# MCUandExtra.net
KiCad netlist of a schematic drawn in Altium Designer
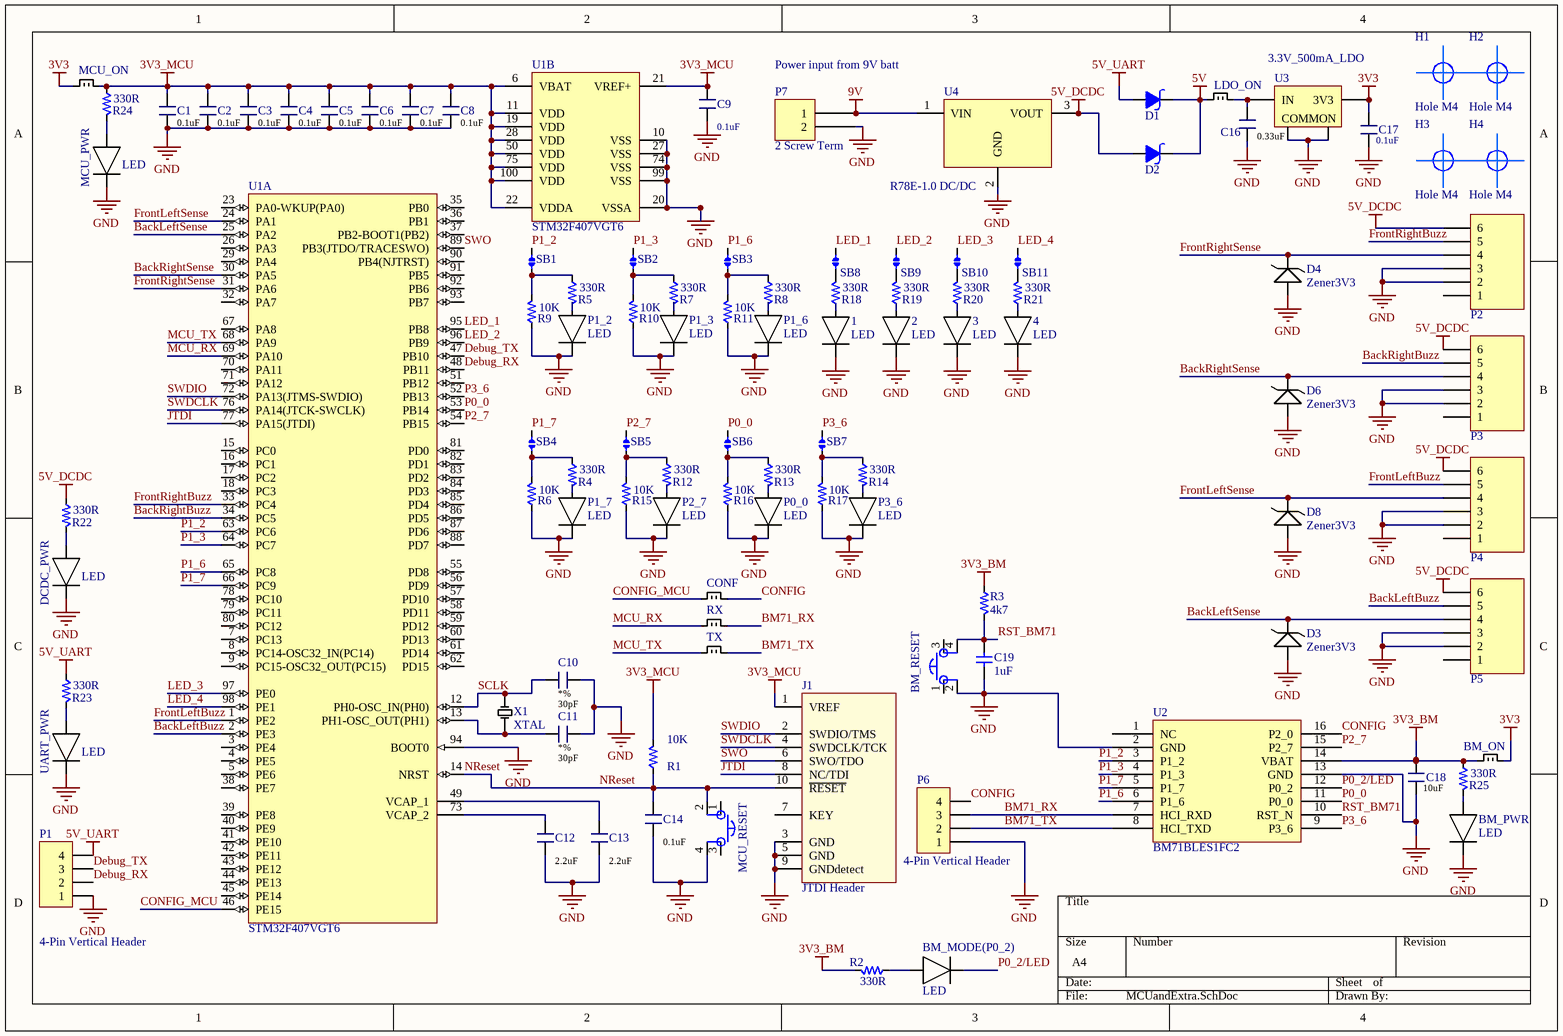
[diagram p0: MCUandExtra.SchDoc]

(export (version "E")
  (design (tool "Eeschema 10.0.6"))
  (components
    (comp (ref "1")
      (value "LED")
      (footprint "SMD_0603_LED")
      (libsource (lib "0603 LED") (part "SMD_0603_LED"))
    )
    (comp (ref "2")
      (value "LED")
      (footprint "SMD_0603_LED")
      (libsource (lib "0603 LED") (part "SMD_0603_LED"))
    )
    (comp (ref "3")
      (value "LED")
      (footprint "SMD_0603_LED")
      (libsource (lib "0603 LED") (part "SMD_0603_LED"))
    )
    (comp (ref "4")
      (value "LED")
      (footprint "SMD_0603_LED")
      (libsource (lib "0603 LED") (part "SMD_0603_LED"))
    )
    (comp (ref "BM_MODE(P0_2)")
      (value "LED")
      (footprint "SMD_0603_LED")
      (libsource (lib "0603 LED") (part "SMD_0603_LED"))
    )
    (comp (ref "BM_ON")
      (value "2.54Jump")
      (footprint "Jumper")
      (description "WM23943-ND")
      (libsource (lib "2.54HeaderJumper") (part "Jumper"))
    )
    (comp (ref "BM_PWR")
      (value "LED")
      (footprint "SMD_0603_LED")
      (libsource (lib "0603 LED") (part "SMD_0603_LED"))
    )
    (comp (ref "BM_RESET")
      (value "Tactile Switch")
      (footprint "C&K 4 pin Tactile Switch")
      (libsource (lib "C&K 4 Pin Tactile Switch") (part "C&K Tactile Switch"))
    )
    (comp (ref "C1")
      (value "SCH_GENERIC_CAPACITOR_0603")
      (footprint "PCB_GENERIC_SMD_0603")
      (description "Generic SMD capacitor 0603")
      (fields (field (name "TOLERANCE") "*%") (field (name "CAPACITANCE") "0.1uF"))
      (libsource (lib "Generic 0603 Capacitor") (part "SCH_GENERIC_CAPACITOR_0603"))
    )
    (comp (ref "C2")
      (value "SCH_GENERIC_CAPACITOR_0603")
      (footprint "PCB_GENERIC_SMD_0603")
      (description "Generic SMD capacitor 0603")
      (fields (field (name "TOLERANCE") "*%") (field (name "CAPACITANCE") "0.1uF"))
      (libsource (lib "Generic 0603 Capacitor") (part "SCH_GENERIC_CAPACITOR_0603"))
    )
    (comp (ref "C3")
      (value "SCH_GENERIC_CAPACITOR_0603")
      (footprint "PCB_GENERIC_SMD_0603")
      (description "Generic SMD capacitor 0603")
      (fields (field (name "TOLERANCE") "*%") (field (name "CAPACITANCE") "0.1uF"))
      (libsource (lib "Generic 0603 Capacitor") (part "SCH_GENERIC_CAPACITOR_0603"))
    )
    (comp (ref "C4")
      (value "SCH_GENERIC_CAPACITOR_0603")
      (footprint "PCB_GENERIC_SMD_0603")
      (description "Generic SMD capacitor 0603")
      (fields (field (name "TOLERANCE") "*%") (field (name "CAPACITANCE") "0.1uF"))
      (libsource (lib "Generic 0603 Capacitor") (part "SCH_GENERIC_CAPACITOR_0603"))
    )
    (comp (ref "C5")
      (value "SCH_GENERIC_CAPACITOR_0603")
      (footprint "PCB_GENERIC_SMD_0603")
      (description "Generic SMD capacitor 0603")
      (fields (field (name "TOLERANCE") "*%") (field (name "CAPACITANCE") "0.1uF"))
      (libsource (lib "Generic 0603 Capacitor") (part "SCH_GENERIC_CAPACITOR_0603"))
    )
    (comp (ref "C6")
      (value "SCH_GENERIC_CAPACITOR_0603")
      (footprint "PCB_GENERIC_SMD_0603")
      (description "Generic SMD capacitor 0603")
      (fields (field (name "TOLERANCE") "*%") (field (name "CAPACITANCE") "0.1uF"))
      (libsource (lib "Generic 0603 Capacitor") (part "SCH_GENERIC_CAPACITOR_0603"))
    )
    (comp (ref "C7")
      (value "SCH_GENERIC_CAPACITOR_0603")
      (footprint "PCB_GENERIC_SMD_0603")
      (description "Generic SMD capacitor 0603")
      (fields (field (name "TOLERANCE") "*%") (field (name "CAPACITANCE") "0.1uF"))
      (libsource (lib "Generic 0603 Capacitor") (part "SCH_GENERIC_CAPACITOR_0603"))
    )
    (comp (ref "C8")
      (value "SCH_GENERIC_CAPACITOR_0603")
      (footprint "PCB_GENERIC_SMD_0603")
      (description "Generic SMD capacitor 0603")
      (fields (field (name "TOLERANCE") "*%") (field (name "CAPACITANCE") "0.1uF"))
      (libsource (lib "Generic 0603 Capacitor") (part "SCH_GENERIC_CAPACITOR_0603"))
    )
    (comp (ref "C9")
      (value "SCH_GENERIC_CAPACITOR_0603")
      (footprint "PCB_GENERIC_SMD_0603")
      (description "Generic SMD capacitor 0603")
      (fields (field (name "CAPACITANCE") "0.1uF"))
      (libsource (lib "Generic 0603 Capacitor") (part "SCH_GENERIC_CAPACITOR_0603"))
    )
    (comp (ref "C10")
      (value "SCH_GENERIC_CAPACITOR_0603")
      (footprint "PCB_GENERIC_SMD_0603")
      (description "Generic SMD capacitor 0603")
      (fields (field (name "TOLERANCE") "*%") (field (name "CAPACITANCE") "30pF"))
      (libsource (lib "Capacitors") (part "SCH_GENERIC_CAPACITOR_0603"))
    )
    (comp (ref "C11")
      (value "SCH_GENERIC_CAPACITOR_0603")
      (footprint "PCB_GENERIC_SMD_0603")
      (description "Generic SMD capacitor 0603")
      (fields (field (name "TOLERANCE") "*%") (field (name "CAPACITANCE") "30pF"))
      (libsource (lib "Capacitors") (part "SCH_GENERIC_CAPACITOR_0603"))
    )
    (comp (ref "C12")
      (value "SCH_GENERIC_CAPACITOR_0603")
      (footprint "PCB_GENERIC_SMD_0603")
      (description "Generic SMD capacitor 0603")
      (fields (field (name "TOLERANCE") "*%") (field (name "CAPACITANCE") "2.2uF"))
      (libsource (lib "Capacitors") (part "SCH_GENERIC_CAPACITOR_0603"))
    )
    (comp (ref "C13")
      (value "SCH_GENERIC_CAPACITOR_0603")
      (footprint "PCB_GENERIC_SMD_0603")
      (description "Generic SMD capacitor 0603")
      (fields (field (name "TOLERANCE") "*%") (field (name "CAPACITANCE") "2.2uF"))
      (libsource (lib "Capacitors") (part "SCH_GENERIC_CAPACITOR_0603"))
    )
    (comp (ref "C14")
      (value "SCH_GENERIC_CAPACITOR_0603")
      (footprint "PCB_GENERIC_SMD_0603")
      (description "Generic SMD capacitor 0603")
      (fields (field (name "TOLERANCE") "*%") (field (name "CAPACITANCE") "0.1uF"))
      (libsource (lib "Capacitors") (part "SCH_GENERIC_CAPACITOR_0603"))
    )
    (comp (ref "C16")
      (value "SCH_GENERIC_CAPACITOR_0603")
      (footprint "PCB_GENERIC_SMD_0603")
      (description "Generic SMD capacitor 0603")
      (fields (field (name "CAPACITANCE") "0.33uF") (field (name "TOLERANCE") "*%"))
      (libsource (lib "Generic 0603 Capacitor") (part "SCH_GENERIC_CAPACITOR_0603"))
    )
    (comp (ref "C17")
      (value "SCH_GENERIC_CAPACITOR_0603")
      (footprint "PCB_GENERIC_SMD_0603")
      (description "Generic SMD capacitor 0603")
      (fields (field (name "CAPACITANCE") "0.1uF"))
      (libsource (lib "Generic 0603 Capacitor") (part "SCH_GENERIC_CAPACITOR_0603"))
    )
    (comp (ref "C18")
      (value "SCH_GENERIC_CAPACITOR_0603")
      (footprint "PCB_GENERIC_SMD_0603")
      (description "Generic SMD capacitor 0603")
      (fields (field (name "TOLERANCE") "*%") (field (name "CAPACITANCE") "10uF"))
      (libsource (lib "Capacitors") (part "SCH_GENERIC_CAPACITOR_0603"))
    )
    (comp (ref "C19")
      (value "1uF")
      (footprint "PCB_GENERIC_SMD_0603")
      (description "CAP CER 0603 1uF 16V X5R 20%")
      (fields (field (name "TOLERANCE") "20%") (field (name "VOLTAGE") "16V"))
      (libsource (lib "CAP-0603") (part "C060-0001U-00"))
    )
    (comp (ref "CONF")
      (value "2.54Jump")
      (footprint "Jumper")
      (description "WM23943-ND")
      (libsource (lib "2.54HeaderJumper") (part "Jumper"))
    )
    (comp (ref "D1")
      (value "ONSEMI_MBRM110LT1G")
      (footprint "ON Semi Schottky Diode - MBRM110LT1G")
      (description "DIODE SCHOTTKY 10V 1A")
      (libsource (lib "ON Semi Schottky Diode") (part "ONSEMI_MBRM110LT1G"))
    )
    (comp (ref "D2")
      (value "ONSEMI_MBRM110LT1G")
      (footprint "ON Semi Schottky Diode - MBRM110LT1G")
      (description "DIODE SCHOTTKY 10V 1A")
      (libsource (lib "ON Semi Schottky Diode") (part "ONSEMI_MBRM110LT1G"))
    )
    (comp (ref "D3")
      (value "Zener3V3")
      (footprint "Zener3V3")
      (description "DZ2W03300LCT-ND")
      (libsource (lib "Zener3V3") (part "DZ2W03300LCT-ND"))
    )
    (comp (ref "D4")
      (value "Zener3V3")
      (footprint "Zener3V3")
      (description "DZ2W03300LCT-ND")
      (libsource (lib "Zener3V3") (part "DZ2W03300LCT-ND"))
    )
    (comp (ref "D6")
      (value "Zener3V3")
      (footprint "Zener3V3")
      (description "DZ2W03300LCT-ND")
      (libsource (lib "Zener3V3") (part "DZ2W03300LCT-ND"))
    )
    (comp (ref "D8")
      (value "Zener3V3")
      (footprint "Zener3V3")
      (description "DZ2W03300LCT-ND")
      (libsource (lib "Zener3V3") (part "DZ2W03300LCT-ND"))
    )
    (comp (ref "DCDC_PWR")
      (value "LED")
      (footprint "SMD_0603_LED")
      (libsource (lib "0603 LED") (part "SMD_0603_LED"))
    )
    (comp (ref "H1") (value "Hole M4") (footprint "M4_Hole") (libsource (lib "M4") (part "Component_1")))
    (comp (ref "H2") (value "Hole M4") (footprint "M4_Hole") (libsource (lib "M4") (part "Component_1")))
    (comp (ref "H3") (value "Hole M4") (footprint "M4_Hole") (libsource (lib "M4") (part "Component_1")))
    (comp (ref "H4") (value "Hole M4") (footprint "M4_Hole") (libsource (lib "M4") (part "Component_1")))
    (comp (ref "J1")
      (value "JTDI Header")
      (footprint "CONN-50mil-10POS-SMD")
      (description "ARM Cortex-M 10pin connector,shrouded,SMT")
      (libsource (lib "CONN-50mil-cortexM") (part "conn_0.050{dblquote}_cortexM"))
    )
    (comp (ref "LDO_ON")
      (value "2.54Jump")
      (footprint "Jumper")
      (description "WM23943-ND")
      (libsource (lib "2.54HeaderJumper") (part "Jumper"))
    )
    (comp (ref "MCU_ON")
      (value "2.54Jump")
      (footprint "Jumper")
      (description "WM23943-ND")
      (libsource (lib "2.54HeaderJumper") (part "Jumper"))
    )
    (comp (ref "MCU_PWR")
      (value "LED")
      (footprint "SMD_0603_LED")
      (libsource (lib "0603 LED") (part "SMD_0603_LED"))
    )
    (comp (ref "MCU_RESET")
      (value "Tactile Switch")
      (footprint "C&K 4 pin Tactile Switch")
      (libsource (lib "C&K 4 Pin Tactile Switch") (part "C&K Tactile Switch"))
    )
    (comp (ref "P0_0")
      (value "LED")
      (footprint "SMD_0603_LED")
      (libsource (lib "0603 LED") (part "SMD_0603_LED"))
    )
    (comp (ref "P1")
      (value "4-Pin Vertical Header")
      (footprint "4-Pin Vertical Header")
      (fields (field (name "MANUFACTURER") "Sullins"))
      (libsource (lib "4 Pin 100 mil Vertical Header - Through Hole") (part "4-Pin Vertical Header"))
    )
    (comp (ref "P1_2")
      (value "LED")
      (footprint "SMD_0603_LED")
      (libsource (lib "0603 LED") (part "SMD_0603_LED"))
    )
    (comp (ref "P1_3")
      (value "LED")
      (footprint "SMD_0603_LED")
      (libsource (lib "0603 LED") (part "SMD_0603_LED"))
    )
    (comp (ref "P1_6")
      (value "LED")
      (footprint "SMD_0603_LED")
      (libsource (lib "0603 LED") (part "SMD_0603_LED"))
    )
    (comp (ref "P1_7")
      (value "LED")
      (footprint "SMD_0603_LED")
      (libsource (lib "0603 LED") (part "SMD_0603_LED"))
    )
    (comp (ref "P2")
      (value "SCH_MLX_MICROFIT_3X2")
      (footprint "PCB_MLX_MICROFIT_3X2")
      (libsource (lib "Molex Microfit 3.0 3x2") (part "SCH_MLX_MICROFIT_3X2"))
    )
    (comp (ref "P2_7")
      (value "LED")
      (footprint "SMD_0603_LED")
      (libsource (lib "0603 LED") (part "SMD_0603_LED"))
    )
    (comp (ref "P3")
      (value "SCH_MLX_MICROFIT_3X2")
      (footprint "PCB_MLX_MICROFIT_3X2")
      (libsource (lib "Molex Microfit 3.0 3x2") (part "SCH_MLX_MICROFIT_3X2"))
    )
    (comp (ref "P3_6")
      (value "LED")
      (footprint "SMD_0603_LED")
      (libsource (lib "0603 LED") (part "SMD_0603_LED"))
    )
    (comp (ref "P4")
      (value "SCH_MLX_MICROFIT_3X2")
      (footprint "PCB_MLX_MICROFIT_3X2")
      (libsource (lib "Molex Microfit 3.0 3x2") (part "SCH_MLX_MICROFIT_3X2"))
    )
    (comp (ref "P5")
      (value "SCH_MLX_MICROFIT_3X2")
      (footprint "PCB_MLX_MICROFIT_3X2")
      (libsource (lib "Molex Microfit 3.0 3x2") (part "SCH_MLX_MICROFIT_3X2"))
    )
    (comp (ref "P6")
      (value "4-Pin Vertical Header")
      (footprint "4-Pin Vertical Header")
      (fields (field (name "MANUFACTURER") "Sullins"))
      (libsource (lib "4 Pin 100 mil Vertical Header - Through Hole") (part "4-Pin Vertical Header"))
    )
    (comp (ref "P7")
      (value "2 Screw Term")
      (footprint "PCBComponent_1")
      (libsource (lib "2_Pin_ScrewTerm") (part "2 Screw Term"))
    )
    (comp (ref "R1")
      (value "SCH_GENERIC_RESISTOR_0603")
      (footprint "PCB_GENERIC_SMD_0603")
      (description "Generic SMD resistor 0603")
      (fields (field (name "RESISTANCE") "10K"))
      (libsource (lib "Resistors") (part "SCH_GENERIC_RESISTOR_0603"))
    )
    (comp (ref "R2")
      (value "SCH_GENERIC_RESISTOR_0603")
      (footprint "PCB_GENERIC_SMD_0603")
      (description "Generic SMD resistor 0603")
      (fields (field (name "RESISTANCE") "330R"))
      (libsource (lib "Resistors") (part "SCH_GENERIC_RESISTOR_0603"))
    )
    (comp (ref "R3")
      (value "SCH_GENERIC_RESISTOR_0603")
      (footprint "PCB_GENERIC_SMD_0603")
      (description "Generic SMD resistor 0603")
      (fields (field (name "RESISTANCE") "4k7"))
      (libsource (lib "Resistors") (part "SCH_GENERIC_RESISTOR_0603"))
    )
    (comp (ref "R4")
      (value "SCH_GENERIC_RESISTOR_0603")
      (footprint "PCB_GENERIC_SMD_0603")
      (description "Generic SMD resistor 0603")
      (fields (field (name "RESISTANCE") "330R"))
      (libsource (lib "Generic 0603 Resistor") (part "SCH_GENERIC_RESISTOR_0603"))
    )
    (comp (ref "R5")
      (value "SCH_GENERIC_RESISTOR_0603")
      (footprint "PCB_GENERIC_SMD_0603")
      (description "Generic SMD resistor 0603")
      (fields (field (name "RESISTANCE") "330R"))
      (libsource (lib "Generic 0603 Resistor") (part "SCH_GENERIC_RESISTOR_0603"))
    )
    (comp (ref "R6")
      (value "SCH_GENERIC_RESISTOR_0603")
      (footprint "PCB_GENERIC_SMD_0603")
      (description "Generic SMD resistor 0603")
      (fields (field (name "RESISTANCE") "10K"))
      (libsource (lib "Generic 0603 Resistor") (part "SCH_GENERIC_RESISTOR_0603"))
    )
    (comp (ref "R7")
      (value "SCH_GENERIC_RESISTOR_0603")
      (footprint "PCB_GENERIC_SMD_0603")
      (description "Generic SMD resistor 0603")
      (fields (field (name "RESISTANCE") "330R"))
      (libsource (lib "Generic 0603 Resistor") (part "SCH_GENERIC_RESISTOR_0603"))
    )
    (comp (ref "R8")
      (value "SCH_GENERIC_RESISTOR_0603")
      (footprint "PCB_GENERIC_SMD_0603")
      (description "Generic SMD resistor 0603")
      (fields (field (name "RESISTANCE") "330R"))
      (libsource (lib "Generic 0603 Resistor") (part "SCH_GENERIC_RESISTOR_0603"))
    )
    (comp (ref "R9")
      (value "SCH_GENERIC_RESISTOR_0603")
      (footprint "PCB_GENERIC_SMD_0603")
      (description "Generic SMD resistor 0603")
      (fields (field (name "RESISTANCE") "10K"))
      (libsource (lib "Generic 0603 Resistor") (part "SCH_GENERIC_RESISTOR_0603"))
    )
    (comp (ref "R10")
      (value "SCH_GENERIC_RESISTOR_0603")
      (footprint "PCB_GENERIC_SMD_0603")
      (description "Generic SMD resistor 0603")
      (fields (field (name "RESISTANCE") "10K"))
      (libsource (lib "Generic 0603 Resistor") (part "SCH_GENERIC_RESISTOR_0603"))
    )
    (comp (ref "R11")
      (value "SCH_GENERIC_RESISTOR_0603")
      (footprint "PCB_GENERIC_SMD_0603")
      (description "Generic SMD resistor 0603")
      (fields (field (name "RESISTANCE") "10K"))
      (libsource (lib "Generic 0603 Resistor") (part "SCH_GENERIC_RESISTOR_0603"))
    )
    (comp (ref "R12")
      (value "SCH_GENERIC_RESISTOR_0603")
      (footprint "PCB_GENERIC_SMD_0603")
      (description "Generic SMD resistor 0603")
      (fields (field (name "RESISTANCE") "330R"))
      (libsource (lib "Generic 0603 Resistor") (part "SCH_GENERIC_RESISTOR_0603"))
    )
    (comp (ref "R13")
      (value "SCH_GENERIC_RESISTOR_0603")
      (footprint "PCB_GENERIC_SMD_0603")
      (description "Generic SMD resistor 0603")
      (fields (field (name "RESISTANCE") "330R"))
      (libsource (lib "Generic 0603 Resistor") (part "SCH_GENERIC_RESISTOR_0603"))
    )
    (comp (ref "R14")
      (value "SCH_GENERIC_RESISTOR_0603")
      (footprint "PCB_GENERIC_SMD_0603")
      (description "Generic SMD resistor 0603")
      (fields (field (name "RESISTANCE") "330R"))
      (libsource (lib "Generic 0603 Resistor") (part "SCH_GENERIC_RESISTOR_0603"))
    )
    (comp (ref "R15")
      (value "SCH_GENERIC_RESISTOR_0603")
      (footprint "PCB_GENERIC_SMD_0603")
      (description "Generic SMD resistor 0603")
      (fields (field (name "RESISTANCE") "10K"))
      (libsource (lib "Generic 0603 Resistor") (part "SCH_GENERIC_RESISTOR_0603"))
    )
    (comp (ref "R16")
      (value "SCH_GENERIC_RESISTOR_0603")
      (footprint "PCB_GENERIC_SMD_0603")
      (description "Generic SMD resistor 0603")
      (fields (field (name "RESISTANCE") "10K"))
      (libsource (lib "Generic 0603 Resistor") (part "SCH_GENERIC_RESISTOR_0603"))
    )
    (comp (ref "R17")
      (value "SCH_GENERIC_RESISTOR_0603")
      (footprint "PCB_GENERIC_SMD_0603")
      (description "Generic SMD resistor 0603")
      (fields (field (name "RESISTANCE") "10K"))
      (libsource (lib "Generic 0603 Resistor") (part "SCH_GENERIC_RESISTOR_0603"))
    )
    (comp (ref "R18")
      (value "SCH_GENERIC_RESISTOR_0603")
      (footprint "PCB_GENERIC_SMD_0603")
      (description "Generic SMD resistor 0603")
      (fields (field (name "RESISTANCE") "330R"))
      (libsource (lib "Generic 0603 Resistor") (part "SCH_GENERIC_RESISTOR_0603"))
    )
    (comp (ref "R19")
      (value "SCH_GENERIC_RESISTOR_0603")
      (footprint "PCB_GENERIC_SMD_0603")
      (description "Generic SMD resistor 0603")
      (fields (field (name "RESISTANCE") "330R"))
      (libsource (lib "Generic 0603 Resistor") (part "SCH_GENERIC_RESISTOR_0603"))
    )
    (comp (ref "R20")
      (value "SCH_GENERIC_RESISTOR_0603")
      (footprint "PCB_GENERIC_SMD_0603")
      (description "Generic SMD resistor 0603")
      (fields (field (name "RESISTANCE") "330R"))
      (libsource (lib "Generic 0603 Resistor") (part "SCH_GENERIC_RESISTOR_0603"))
    )
    (comp (ref "R21")
      (value "SCH_GENERIC_RESISTOR_0603")
      (footprint "PCB_GENERIC_SMD_0603")
      (description "Generic SMD resistor 0603")
      (fields (field (name "RESISTANCE") "330R"))
      (libsource (lib "Generic 0603 Resistor") (part "SCH_GENERIC_RESISTOR_0603"))
    )
    (comp (ref "R22")
      (value "SCH_GENERIC_RESISTOR_0603")
      (footprint "PCB_GENERIC_SMD_0603")
      (description "Generic SMD resistor 0603")
      (fields (field (name "RESISTANCE") "330R"))
      (libsource (lib "Generic 0603 Resistor") (part "SCH_GENERIC_RESISTOR_0603"))
    )
    (comp (ref "R23")
      (value "SCH_GENERIC_RESISTOR_0603")
      (footprint "PCB_GENERIC_SMD_0603")
      (description "Generic SMD resistor 0603")
      (fields (field (name "RESISTANCE") "330R"))
      (libsource (lib "Generic 0603 Resistor") (part "SCH_GENERIC_RESISTOR_0603"))
    )
    (comp (ref "R24")
      (value "SCH_GENERIC_RESISTOR_0603")
      (footprint "PCB_GENERIC_SMD_0603")
      (description "Generic SMD resistor 0603")
      (fields (field (name "RESISTANCE") "330R"))
      (libsource (lib "Generic 0603 Resistor") (part "SCH_GENERIC_RESISTOR_0603"))
    )
    (comp (ref "R25")
      (value "SCH_GENERIC_RESISTOR_0603")
      (footprint "PCB_GENERIC_SMD_0603")
      (description "Generic SMD resistor 0603")
      (fields (field (name "RESISTANCE") "330R"))
      (libsource (lib "Generic 0603 Resistor") (part "SCH_GENERIC_RESISTOR_0603"))
    )
    (comp (ref "RX")
      (value "2.54Jump")
      (footprint "Jumper")
      (description "WM23943-ND")
      (libsource (lib "2.54HeaderJumper") (part "Jumper"))
    )
    (comp (ref "SB1")
      (value "N/O")
      (footprint "SB_NO")
      (description "Solder Bridge, Normally Open")
      (libsource (lib "SolderJumper20mil") (part "SB_NO"))
    )
    (comp (ref "SB2")
      (value "N/O")
      (footprint "SB_NO")
      (description "Solder Bridge, Normally Open")
      (libsource (lib "SolderJumper20mil") (part "SB_NO"))
    )
    (comp (ref "SB3")
      (value "N/O")
      (footprint "SB_NO")
      (description "Solder Bridge, Normally Open")
      (libsource (lib "SolderJumper20mil") (part "SB_NO"))
    )
    (comp (ref "SB4")
      (value "N/O")
      (footprint "SB_NO")
      (description "Solder Bridge, Normally Open")
      (libsource (lib "SolderJumper20mil") (part "SB_NO"))
    )
    (comp (ref "SB5")
      (value "N/O")
      (footprint "SB_NO")
      (description "Solder Bridge, Normally Open")
      (libsource (lib "SolderJumper20mil") (part "SB_NO"))
    )
    (comp (ref "SB6")
      (value "N/O")
      (footprint "SB_NO")
      (description "Solder Bridge, Normally Open")
      (libsource (lib "SolderJumper20mil") (part "SB_NO"))
    )
    (comp (ref "SB7")
      (value "N/O")
      (footprint "SB_NO")
      (description "Solder Bridge, Normally Open")
      (libsource (lib "SolderJumper20mil") (part "SB_NO"))
    )
    (comp (ref "SB8")
      (value "N/O")
      (footprint "SB_NO")
      (description "Solder Bridge, Normally Open")
      (libsource (lib "SolderJumper20mil") (part "SB_NO"))
    )
    (comp (ref "SB9")
      (value "N/O")
      (footprint "SB_NO")
      (description "Solder Bridge, Normally Open")
      (libsource (lib "SolderJumper20mil") (part "SB_NO"))
    )
    (comp (ref "SB10")
      (value "N/O")
      (footprint "SB_NO")
      (description "Solder Bridge, Normally Open")
      (libsource (lib "SolderJumper20mil") (part "SB_NO"))
    )
    (comp (ref "SB11")
      (value "N/O")
      (footprint "SB_NO")
      (description "Solder Bridge, Normally Open")
      (libsource (lib "SolderJumper20mil") (part "SB_NO"))
    )
    (comp (ref "TX")
      (value "2.54Jump")
      (footprint "Jumper")
      (description "WM23943-ND")
      (libsource (lib "2.54HeaderJumper") (part "Jumper"))
    )
    (comp (ref "U1")
      (value "STM32F407VGT6")
      (footprint "STM-LQFP100_N")
      (fields (field (name "MANUFACTURER") "STMicroelectronics"))
      (libsource (lib "STMicroelectronics STM32 F4") (part "STM32F407VGT6"))
    )
    (comp (ref "U2")
      (value "BM71BLES1FC2")
      (footprint "BM71BLES1FC2")
      (description "BM71 Bluetooth Module")
      (libsource (lib "BM71BLES1FC2") (part "BM71 Bluetooth Module"))
    )
    (comp (ref "U3")
      (value "3.3V_500mA_LDO")
      (footprint "3.3V_500mA_LDO")
      (description "IC REG LIN 3.3V 500MA SOT223-4")
      (libsource (lib "3.3_500mA_TI") (part "3.3V_500mA"))
    )
    (comp (ref "U4")
      (value "R78E-1.0 DC/DC")
      (footprint "R78-1.0")
      (libsource (lib "Recom R78E-1.0") (part "R78E-1.0"))
    )
    (comp (ref "UART_PWR")
      (value "LED")
      (footprint "SMD_0603_LED")
      (libsource (lib "0603 LED") (part "SMD_0603_LED"))
    )
    (comp (ref "X1") (value "XTAL") (footprint "CRYSTAL_8MHZ") (libsource (lib "Crystal") (part "Crystal")))
  )
  (nets
    (net (code "1") (name "/BM71_RX") (class "Default")
      (node (ref "P6") (pin "3") (pinfunction "3_3") (pintype "passive"))
      (node (ref "RX") (pin "2") (pinfunction "2_2") (pintype "passive"))
      (node (ref "U2") (pin "7") (pinfunction "HCI_RXD_7") (pintype "passive"))
    )
    (net (code "2") (name "/BM71_TX") (class "Default")
      (node (ref "P6") (pin "2") (pinfunction "2_2") (pintype "passive"))
      (node (ref "TX") (pin "2") (pinfunction "2_2") (pintype "passive"))
      (node (ref "U2") (pin "8") (pinfunction "HCI_TXD_8") (pintype "passive"))
    )
    (net (code "3") (name "/BackLeftBuzz") (class "Default")
      (node (ref "P5") (pin "5") (pinfunction "5_5") (pintype "passive"))
      (node (ref "U1") (pin "2") (pinfunction "PE3_2") (pintype "bidirectional"))
    )
    (net (code "4") (name "/BackLeftSense") (class "Default")
      (node (ref "D3") (pin "1") (pinfunction "1_1") (pintype "passive"))
      (node (ref "P5") (pin "4") (pinfunction "4_4") (pintype "passive"))
      (node (ref "U1") (pin "25") (pinfunction "PA2_25") (pintype "bidirectional"))
    )
    (net (code "5") (name "/BackRightBuzz") (class "Default")
      (node (ref "P3") (pin "5") (pinfunction "5_5") (pintype "passive"))
      (node (ref "U1") (pin "34") (pinfunction "PC5_34") (pintype "bidirectional"))
    )
    (net (code "6") (name "/BackRightSense") (class "Default")
      (node (ref "D6") (pin "1") (pinfunction "1_1") (pintype "passive"))
      (node (ref "P3") (pin "4") (pinfunction "4_4") (pintype "passive"))
      (node (ref "U1") (pin "30") (pinfunction "PA5_30") (pintype "bidirectional"))
    )
    (net (code "7") (name "/CONFIG") (class "Default")
      (node (ref "CONF") (pin "2") (pinfunction "2_2") (pintype "passive"))
      (node (ref "P6") (pin "4") (pinfunction "4_4") (pintype "passive"))
      (node (ref "U2") (pin "16") (pinfunction "P2_0_16") (pintype "passive"))
    )
    (net (code "8") (name "/CONFIG_MCU") (class "Default")
      (node (ref "CONF") (pin "1") (pinfunction "1_1") (pintype "passive"))
      (node (ref "U1") (pin "46") (pinfunction "PE15_46") (pintype "bidirectional"))
    )
    (net (code "9") (name "/Debug_RX") (class "Default")
      (node (ref "P1") (pin "2") (pinfunction "2_2") (pintype "passive"))
      (node (ref "U1") (pin "48") (pinfunction "PB11_48") (pintype "bidirectional"))
    )
    (net (code "10") (name "/Debug_TX") (class "Default")
      (node (ref "P1") (pin "3") (pinfunction "3_3") (pintype "passive"))
      (node (ref "U1") (pin "47") (pinfunction "PB10_47") (pintype "bidirectional"))
    )
    (net (code "11") (name "/FrontLeftBuzz") (class "Default")
      (node (ref "P4") (pin "5") (pinfunction "5_5") (pintype "passive"))
      (node (ref "U1") (pin "1") (pinfunction "PE2_1") (pintype "bidirectional"))
    )
    (net (code "12") (name "/FrontLeftSense") (class "Default")
      (node (ref "D8") (pin "1") (pinfunction "1_1") (pintype "passive"))
      (node (ref "P4") (pin "4") (pinfunction "4_4") (pintype "passive"))
      (node (ref "U1") (pin "24") (pinfunction "PA1_24") (pintype "bidirectional"))
    )
    (net (code "13") (name "/FrontRightBuzz") (class "Default")
      (node (ref "P2") (pin "5") (pinfunction "5_5") (pintype "passive"))
      (node (ref "U1") (pin "33") (pinfunction "PC4_33") (pintype "bidirectional"))
    )
    (net (code "14") (name "/FrontRightSense") (class "Default")
      (node (ref "D4") (pin "1") (pinfunction "1_1") (pintype "passive"))
      (node (ref "P2") (pin "4") (pinfunction "4_4") (pintype "passive"))
      (node (ref "U1") (pin "31") (pinfunction "PA6_31") (pintype "bidirectional"))
    )
    (net (code "15") (name "/JTDI") (class "Default")
      (node (ref "J1") (pin "8") (pinfunction "NC/TDI_8") (pintype "passive"))
      (node (ref "U1") (pin "77") (pinfunction "PA15(JTDI)_77") (pintype "bidirectional"))
    )
    (net (code "16") (name "/LED_1") (class "Default")
      (node (ref "SB8") (pin "2") (pinfunction "2_2") (pintype "passive"))
      (node (ref "U1") (pin "95") (pinfunction "PB8_95") (pintype "bidirectional"))
    )
    (net (code "17") (name "/LED_2") (class "Default")
      (node (ref "SB9") (pin "2") (pinfunction "2_2") (pintype "passive"))
      (node (ref "U1") (pin "96") (pinfunction "PB9_96") (pintype "bidirectional"))
    )
    (net (code "18") (name "/LED_3") (class "Default")
      (node (ref "SB10") (pin "2") (pinfunction "2_2") (pintype "passive"))
      (node (ref "U1") (pin "97") (pinfunction "PE0_97") (pintype "bidirectional"))
    )
    (net (code "19") (name "/LED_4") (class "Default")
      (node (ref "SB11") (pin "2") (pinfunction "2_2") (pintype "passive"))
      (node (ref "U1") (pin "98") (pinfunction "PE1_98") (pintype "bidirectional"))
    )
    (net (code "20") (name "/MCU_RX") (class "Default")
      (node (ref "RX") (pin "1") (pinfunction "1_1") (pintype "passive"))
      (node (ref "U1") (pin "69") (pinfunction "PA10_69") (pintype "bidirectional"))
    )
    (net (code "21") (name "/MCU_TX") (class "Default")
      (node (ref "TX") (pin "1") (pinfunction "1_1") (pintype "passive"))
      (node (ref "U1") (pin "68") (pinfunction "PA9_68") (pintype "bidirectional"))
    )
    (net (code "22") (name "/NReset") (class "Default")
      (node (ref "C14") (pin "1") (pinfunction "1_1") (pintype "passive"))
      (node (ref "J1") (pin "10") (pinfunction "~{RESET}_10") (pintype "passive"))
      (node (ref "MCU_RESET") (pin "2") (pinfunction "2_2") (pintype "passive"))
      (node (ref "R1") (pin "1") (pinfunction "1_1") (pintype "passive"))
      (node (ref "U1") (pin "14") (pinfunction "NRST_14") (pintype "bidirectional"))
    )
    (net (code "23") (name "/P0_0") (class "Default")
      (node (ref "SB6") (pin "2") (pinfunction "2_2") (pintype "passive"))
      (node (ref "U1") (pin "53") (pinfunction "PB14_53") (pintype "bidirectional"))
      (node (ref "U2") (pin "11") (pinfunction "P0_0_11") (pintype "passive"))
    )
    (net (code "24") (name "/P0_2{slash}LED") (class "Default")
      (node (ref "BM_MODE(P0_2)") (pin "2") (pinfunction "2_2") (pintype "passive"))
      (node (ref "U2") (pin "12") (pinfunction "P0_2_12") (pintype "passive"))
    )
    (net (code "25") (name "/P1_2") (class "Default")
      (node (ref "SB1") (pin "2") (pinfunction "2_2") (pintype "passive"))
      (node (ref "U1") (pin "63") (pinfunction "PC6_63") (pintype "bidirectional"))
      (node (ref "U2") (pin "3") (pinfunction "P1_2_3") (pintype "passive"))
    )
    (net (code "26") (name "/P1_3") (class "Default")
      (node (ref "SB2") (pin "2") (pinfunction "2_2") (pintype "passive"))
      (node (ref "U1") (pin "64") (pinfunction "PC7_64") (pintype "bidirectional"))
      (node (ref "U2") (pin "4") (pinfunction "P1_3_4") (pintype "passive"))
    )
    (net (code "27") (name "/P1_6") (class "Default")
      (node (ref "SB3") (pin "2") (pinfunction "2_2") (pintype "passive"))
      (node (ref "U1") (pin "65") (pinfunction "PC8_65") (pintype "bidirectional"))
      (node (ref "U2") (pin "6") (pinfunction "P1_6_6") (pintype "passive"))
    )
    (net (code "28") (name "/P1_7") (class "Default")
      (node (ref "SB4") (pin "2") (pinfunction "2_2") (pintype "passive"))
      (node (ref "U1") (pin "66") (pinfunction "PC9_66") (pintype "bidirectional"))
      (node (ref "U2") (pin "5") (pinfunction "P1_7_5") (pintype "passive"))
    )
    (net (code "29") (name "/P2_7") (class "Default")
      (node (ref "SB5") (pin "2") (pinfunction "2_2") (pintype "passive"))
      (node (ref "U1") (pin "54") (pinfunction "PB15_54") (pintype "bidirectional"))
      (node (ref "U2") (pin "15") (pinfunction "P2_7_15") (pintype "passive"))
    )
    (net (code "30") (name "/P3_6") (class "Default")
      (node (ref "SB7") (pin "2") (pinfunction "2_2") (pintype "passive"))
      (node (ref "U1") (pin "52") (pinfunction "PB13_52") (pintype "bidirectional"))
      (node (ref "U2") (pin "9") (pinfunction "P3_6_9") (pintype "passive"))
    )
    (net (code "31") (name "/RST_BM71") (class "Default")
      (node (ref "BM_RESET") (pin "4") (pinfunction "4_4") (pintype "passive"))
      (node (ref "C19") (pin "2") (pinfunction "2_2") (pintype "passive"))
      (node (ref "R3") (pin "2") (pinfunction "2_2") (pintype "passive"))
      (node (ref "U2") (pin "10") (pinfunction "RST_N_10") (pintype "passive"))
    )
    (net (code "32") (name "/SCLK") (class "Default")
      (node (ref "C10") (pin "2") (pinfunction "2_2") (pintype "passive"))
      (node (ref "U1") (pin "12") (pinfunction "PH0-OSC_IN(PH0)_12") (pintype "bidirectional"))
      (node (ref "X1") (pin "1") (pintype "passive"))
    )
    (net (code "33") (name "/SWDCLK") (class "Default")
      (node (ref "J1") (pin "4") (pinfunction "SWDCLK/TCK_4") (pintype "passive"))
      (node (ref "U1") (pin "76") (pinfunction "PA14(JTCK-SWCLK)_76") (pintype "bidirectional"))
    )
    (net (code "34") (name "/SWDIO") (class "Default")
      (node (ref "J1") (pin "2") (pinfunction "SWDIO/TMS_2") (pintype "passive"))
      (node (ref "U1") (pin "72") (pinfunction "PA13(JTMS-SWDIO)_72") (pintype "bidirectional"))
    )
    (net (code "35") (name "/SWO") (class "Default")
      (node (ref "J1") (pin "6") (pinfunction "SWO/TDO_6") (pintype "passive"))
      (node (ref "U1") (pin "89") (pinfunction "PB3(JTDO/TRACESWO)_89") (pintype "bidirectional"))
    )
    (net (code "36") (name "3V3") (class "Default")
      (node (ref "BM_ON") (pin "2") (pinfunction "2_2") (pintype "passive"))
      (node (ref "C17") (pin "2") (pinfunction "2_2") (pintype "passive"))
      (node (ref "MCU_ON") (pin "1") (pinfunction "1_1") (pintype "passive"))
      (node (ref "U3") (pin "3") (pinfunction "3V3_3") (pintype "passive"))
    )
    (net (code "37") (name "3V3_BM") (class "Default")
      (node (ref "BM_ON") (pin "1") (pinfunction "1_1") (pintype "passive"))
      (node (ref "C18") (pin "2") (pinfunction "2_2") (pintype "passive"))
      (node (ref "R2") (pin "2") (pinfunction "2_2") (pintype "passive"))
      (node (ref "R25") (pin "1") (pinfunction "1_1") (pintype "passive"))
      (node (ref "R3") (pin "1") (pinfunction "1_1") (pintype "passive"))
      (node (ref "U2") (pin "14") (pinfunction "VBAT_14") (pintype "passive"))
    )
    (net (code "38") (name "3V3_MCU") (class "Default")
      (node (ref "C1") (pin "2") (pinfunction "2_2") (pintype "passive"))
      (node (ref "C2") (pin "2") (pinfunction "2_2") (pintype "passive"))
      (node (ref "C3") (pin "2") (pinfunction "2_2") (pintype "passive"))
      (node (ref "C4") (pin "2") (pinfunction "2_2") (pintype "passive"))
      (node (ref "C5") (pin "2") (pinfunction "2_2") (pintype "passive"))
      (node (ref "C6") (pin "2") (pinfunction "2_2") (pintype "passive"))
      (node (ref "C7") (pin "2") (pinfunction "2_2") (pintype "passive"))
      (node (ref "C8") (pin "2") (pinfunction "2_2") (pintype "passive"))
      (node (ref "C9") (pin "2") (pinfunction "2_2") (pintype "passive"))
      (node (ref "J1") (pin "1") (pinfunction "VREF_1") (pintype "passive"))
      (node (ref "MCU_ON") (pin "2") (pinfunction "2_2") (pintype "passive"))
      (node (ref "R1") (pin "2") (pinfunction "2_2") (pintype "passive"))
      (node (ref "R24") (pin "1") (pinfunction "1_1") (pintype "passive"))
      (node (ref "U1") (pin "100") (pinfunction "VDD_100") (pintype "power_in"))
      (node (ref "U1") (pin "11") (pinfunction "VDD_11") (pintype "power_in"))
      (node (ref "U1") (pin "19") (pinfunction "VDD_19") (pintype "power_in"))
      (node (ref "U1") (pin "21") (pinfunction "VREF+_21") (pintype "power_in"))
      (node (ref "U1") (pin "22") (pinfunction "VDDA_22") (pintype "power_in"))
      (node (ref "U1") (pin "28") (pinfunction "VDD_28") (pintype "power_in"))
      (node (ref "U1") (pin "50") (pinfunction "VDD_50") (pintype "power_in"))
      (node (ref "U1") (pin "6") (pinfunction "VBAT_6") (pintype "power_in"))
      (node (ref "U1") (pin "75") (pinfunction "VDD_75") (pintype "power_in"))
    )
    (net (code "39") (name "5V") (class "Default")
      (node (ref "D1") (pin "1") (pinfunction "1_1") (pintype "passive"))
      (node (ref "D2") (pin "1") (pinfunction "1_1") (pintype "passive"))
      (node (ref "LDO_ON") (pin "1") (pinfunction "1_1") (pintype "passive"))
    )
    (net (code "40") (name "5V_DCDC") (class "Default")
      (node (ref "D2") (pin "2") (pinfunction "2_2") (pintype "passive"))
      (node (ref "P2") (pin "6") (pinfunction "6_6") (pintype "passive"))
      (node (ref "P3") (pin "6") (pinfunction "6_6") (pintype "passive"))
      (node (ref "P4") (pin "6") (pinfunction "6_6") (pintype "passive"))
      (node (ref "P5") (pin "6") (pinfunction "6_6") (pintype "passive"))
      (node (ref "R22") (pin "1") (pinfunction "1_1") (pintype "passive"))
      (node (ref "U4") (pin "3") (pinfunction "VOUT_3") (pintype "passive"))
    )
    (net (code "41") (name "5V_UART") (class "Default")
      (node (ref "D1") (pin "2") (pinfunction "2_2") (pintype "passive"))
      (node (ref "P1") (pin "4") (pinfunction "4_4") (pintype "passive"))
      (node (ref "R23") (pin "1") (pinfunction "1_1") (pintype "passive"))
    )
    (net (code "42") (name "9V") (class "Default")
      (node (ref "P7") (pin "1") (pinfunction "1_1") (pintype "passive"))
      (node (ref "U4") (pin "1") (pinfunction "VIN_1") (pintype "passive"))
    )
    (net (code "43") (name "GND") (class "Default")
      (node (ref "1") (pin "2") (pinfunction "2_2") (pintype "passive"))
      (node (ref "2") (pin "2") (pinfunction "2_2") (pintype "passive"))
      (node (ref "3") (pin "2") (pinfunction "2_2") (pintype "passive"))
      (node (ref "4") (pin "2") (pinfunction "2_2") (pintype "passive"))
      (node (ref "BM_PWR") (pin "2") (pinfunction "2_2") (pintype "passive"))
      (node (ref "BM_RESET") (pin "2") (pinfunction "2_2") (pintype "passive"))
      (node (ref "C1") (pin "1") (pinfunction "1_1") (pintype "passive"))
      (node (ref "C10") (pin "1") (pinfunction "1_1") (pintype "passive"))
      (node (ref "C11") (pin "1") (pinfunction "1_1") (pintype "passive"))
      (node (ref "C12") (pin "1") (pinfunction "1_1") (pintype "passive"))
      (node (ref "C13") (pin "1") (pinfunction "1_1") (pintype "passive"))
      (node (ref "C14") (pin "2") (pinfunction "2_2") (pintype "passive"))
      (node (ref "C16") (pin "2") (pinfunction "2_2") (pintype "passive"))
      (node (ref "C17") (pin "1") (pinfunction "1_1") (pintype "passive"))
      (node (ref "C18") (pin "1") (pinfunction "1_1") (pintype "passive"))
      (node (ref "C19") (pin "1") (pinfunction "1_1") (pintype "passive"))
      (node (ref "C2") (pin "1") (pinfunction "1_1") (pintype "passive"))
      (node (ref "C3") (pin "1") (pinfunction "1_1") (pintype "passive"))
      (node (ref "C4") (pin "1") (pinfunction "1_1") (pintype "passive"))
      (node (ref "C5") (pin "1") (pinfunction "1_1") (pintype "passive"))
      (node (ref "C6") (pin "1") (pinfunction "1_1") (pintype "passive"))
      (node (ref "C7") (pin "1") (pinfunction "1_1") (pintype "passive"))
      (node (ref "C8") (pin "1") (pinfunction "1_1") (pintype "passive"))
      (node (ref "C9") (pin "1") (pinfunction "1_1") (pintype "passive"))
      (node (ref "D3") (pin "2") (pinfunction "2_2") (pintype "passive"))
      (node (ref "D4") (pin "2") (pinfunction "2_2") (pintype "passive"))
      (node (ref "D6") (pin "2") (pinfunction "2_2") (pintype "passive"))
      (node (ref "D8") (pin "2") (pinfunction "2_2") (pintype "passive"))
      (node (ref "DCDC_PWR") (pin "2") (pinfunction "2_2") (pintype "passive"))
      (node (ref "J1") (pin "3") (pinfunction "GND_3") (pintype "passive"))
      (node (ref "J1") (pin "5") (pinfunction "GND_5") (pintype "passive"))
      (node (ref "J1") (pin "9") (pinfunction "GNDdetect_9") (pintype "passive"))
      (node (ref "MCU_PWR") (pin "2") (pinfunction "2_2") (pintype "passive"))
      (node (ref "MCU_RESET") (pin "4") (pinfunction "4_4") (pintype "passive"))
      (node (ref "P0_0") (pin "2") (pinfunction "2_2") (pintype "passive"))
      (node (ref "P1") (pin "1") (pinfunction "1_1") (pintype "passive"))
      (node (ref "P1_2") (pin "2") (pinfunction "2_2") (pintype "passive"))
      (node (ref "P1_3") (pin "2") (pinfunction "2_2") (pintype "passive"))
      (node (ref "P1_6") (pin "2") (pinfunction "2_2") (pintype "passive"))
      (node (ref "P1_7") (pin "2") (pinfunction "2_2") (pintype "passive"))
      (node (ref "P2") (pin "2") (pinfunction "2_2") (pintype "passive"))
      (node (ref "P2") (pin "3") (pinfunction "3_3") (pintype "passive"))
      (node (ref "P2_7") (pin "2") (pinfunction "2_2") (pintype "passive"))
      (node (ref "P3") (pin "2") (pinfunction "2_2") (pintype "passive"))
      (node (ref "P3") (pin "3") (pinfunction "3_3") (pintype "passive"))
      (node (ref "P3_6") (pin "2") (pinfunction "2_2") (pintype "passive"))
      (node (ref "P4") (pin "2") (pinfunction "2_2") (pintype "passive"))
      (node (ref "P4") (pin "3") (pinfunction "3_3") (pintype "passive"))
      (node (ref "P5") (pin "2") (pinfunction "2_2") (pintype "passive"))
      (node (ref "P5") (pin "3") (pinfunction "3_3") (pintype "passive"))
      (node (ref "P6") (pin "1") (pinfunction "1_1") (pintype "passive"))
      (node (ref "P7") (pin "2") (pinfunction "2_2") (pintype "passive"))
      (node (ref "R10") (pin "1") (pinfunction "1_1") (pintype "passive"))
      (node (ref "R11") (pin "1") (pinfunction "1_1") (pintype "passive"))
      (node (ref "R15") (pin "1") (pinfunction "1_1") (pintype "passive"))
      (node (ref "R16") (pin "1") (pinfunction "1_1") (pintype "passive"))
      (node (ref "R17") (pin "1") (pinfunction "1_1") (pintype "passive"))
      (node (ref "R6") (pin "1") (pinfunction "1_1") (pintype "passive"))
      (node (ref "R9") (pin "1") (pinfunction "1_1") (pintype "passive"))
      (node (ref "U1") (pin "10") (pinfunction "VSS_10") (pintype "power_in"))
      (node (ref "U1") (pin "20") (pinfunction "VSSA_20") (pintype "power_in"))
      (node (ref "U1") (pin "27") (pinfunction "VSS_27") (pintype "power_in"))
      (node (ref "U1") (pin "74") (pinfunction "VSS_74") (pintype "power_in"))
      (node (ref "U1") (pin "94") (pinfunction "BOOT0_94") (pintype "input"))
      (node (ref "U1") (pin "99") (pinfunction "VSS_99") (pintype "power_in"))
      (node (ref "U2") (pin "13") (pinfunction "GND_13") (pintype "passive"))
      (node (ref "U2") (pin "2") (pinfunction "GND_2") (pintype "passive"))
      (node (ref "U3") (pin "2") (pinfunction "GND_2") (pintype "passive"))
      (node (ref "U3") (pin "4") (pinfunction "GND_4") (pintype "passive"))
      (node (ref "U4") (pin "2") (pinfunction "GND_2") (pintype "passive"))
      (node (ref "UART_PWR") (pin "2") (pinfunction "2_2") (pintype "passive"))
    )
    (net (code "44") (name "Net-(1-Pad1)") (class "Default")
      (node (ref "1") (pin "1") (pinfunction "1_1") (pintype "passive"))
      (node (ref "R18") (pin "1") (pinfunction "1_1") (pintype "passive"))
    )
    (net (code "45") (name "Net-(2-Pad1)") (class "Default")
      (node (ref "2") (pin "1") (pinfunction "1_1") (pintype "passive"))
      (node (ref "R19") (pin "1") (pinfunction "1_1") (pintype "passive"))
    )
    (net (code "46") (name "Net-(3-Pad1)") (class "Default")
      (node (ref "3") (pin "1") (pinfunction "1_1") (pintype "passive"))
      (node (ref "R20") (pin "1") (pinfunction "1_1") (pintype "passive"))
    )
    (net (code "47") (name "Net-(4-Pad1)") (class "Default")
      (node (ref "4") (pin "1") (pinfunction "1_1") (pintype "passive"))
      (node (ref "R21") (pin "1") (pinfunction "1_1") (pintype "passive"))
    )
    (net (code "48") (name "Net-(BM_MODE(P0_2)-Pad1)") (class "Default")
      (node (ref "BM_MODE(P0_2)") (pin "1") (pinfunction "1_1") (pintype "passive"))
      (node (ref "R2") (pin "1") (pinfunction "1_1") (pintype "passive"))
    )
    (net (code "49") (name "Net-(BM_PWR-Pad1)") (class "Default")
      (node (ref "BM_PWR") (pin "1") (pinfunction "1_1") (pintype "passive"))
      (node (ref "R25") (pin "2") (pinfunction "2_2") (pintype "passive"))
    )
    (net (code "50") (name "Net-(DCDC_PWR-Pad1)") (class "Default")
      (node (ref "DCDC_PWR") (pin "1") (pinfunction "1_1") (pintype "passive"))
      (node (ref "R22") (pin "2") (pinfunction "2_2") (pintype "passive"))
    )
    (net (code "51") (name "Net-(MCU_PWR-Pad1)") (class "Default")
      (node (ref "MCU_PWR") (pin "1") (pinfunction "1_1") (pintype "passive"))
      (node (ref "R24") (pin "2") (pinfunction "2_2") (pintype "passive"))
    )
    (net (code "52") (name "Net-(P0_0-Pad1)") (class "Default")
      (node (ref "P0_0") (pin "1") (pinfunction "1_1") (pintype "passive"))
      (node (ref "R13") (pin "2") (pinfunction "2_2") (pintype "passive"))
    )
    (net (code "53") (name "Net-(P1_2-Pad1)") (class "Default")
      (node (ref "P1_2") (pin "1") (pinfunction "1_1") (pintype "passive"))
      (node (ref "R5") (pin "2") (pinfunction "2_2") (pintype "passive"))
    )
    (net (code "54") (name "Net-(P1_3-Pad1)") (class "Default")
      (node (ref "P1_3") (pin "1") (pinfunction "1_1") (pintype "passive"))
      (node (ref "R7") (pin "2") (pinfunction "2_2") (pintype "passive"))
    )
    (net (code "55") (name "Net-(P1_6-Pad1)") (class "Default")
      (node (ref "P1_6") (pin "1") (pinfunction "1_1") (pintype "passive"))
      (node (ref "R8") (pin "2") (pinfunction "2_2") (pintype "passive"))
    )
    (net (code "56") (name "Net-(P1_7-Pad1)") (class "Default")
      (node (ref "P1_7") (pin "1") (pinfunction "1_1") (pintype "passive"))
      (node (ref "R4") (pin "2") (pinfunction "2_2") (pintype "passive"))
    )
    (net (code "57") (name "Net-(P2_7-Pad1)") (class "Default")
      (node (ref "P2_7") (pin "1") (pinfunction "1_1") (pintype "passive"))
      (node (ref "R12") (pin "2") (pinfunction "2_2") (pintype "passive"))
    )
    (net (code "58") (name "Net-(P3_6-Pad1)") (class "Default")
      (node (ref "P3_6") (pin "1") (pinfunction "1_1") (pintype "passive"))
      (node (ref "R14") (pin "2") (pinfunction "2_2") (pintype "passive"))
    )
    (net (code "59") (name "Net-(R4-Pad1)") (class "Default")
      (node (ref "R4") (pin "1") (pinfunction "1_1") (pintype "passive"))
      (node (ref "R6") (pin "2") (pinfunction "2_2") (pintype "passive"))
      (node (ref "SB4") (pin "1") (pinfunction "1_1") (pintype "passive"))
    )
    (net (code "60") (name "Net-(R5-Pad1)") (class "Default")
      (node (ref "R5") (pin "1") (pinfunction "1_1") (pintype "passive"))
      (node (ref "R9") (pin "2") (pinfunction "2_2") (pintype "passive"))
      (node (ref "SB1") (pin "1") (pinfunction "1_1") (pintype "passive"))
    )
    (net (code "61") (name "Net-(R10-Pad2)") (class "Default")
      (node (ref "R10") (pin "2") (pinfunction "2_2") (pintype "passive"))
      (node (ref "R7") (pin "1") (pinfunction "1_1") (pintype "passive"))
      (node (ref "SB2") (pin "1") (pinfunction "1_1") (pintype "passive"))
    )
    (net (code "62") (name "Net-(R11-Pad2)") (class "Default")
      (node (ref "R11") (pin "2") (pinfunction "2_2") (pintype "passive"))
      (node (ref "R8") (pin "1") (pinfunction "1_1") (pintype "passive"))
      (node (ref "SB3") (pin "1") (pinfunction "1_1") (pintype "passive"))
    )
    (net (code "63") (name "Net-(R12-Pad1)") (class "Default")
      (node (ref "R12") (pin "1") (pinfunction "1_1") (pintype "passive"))
      (node (ref "R15") (pin "2") (pinfunction "2_2") (pintype "passive"))
      (node (ref "SB5") (pin "1") (pinfunction "1_1") (pintype "passive"))
    )
    (net (code "64") (name "Net-(R13-Pad1)") (class "Default")
      (node (ref "R13") (pin "1") (pinfunction "1_1") (pintype "passive"))
      (node (ref "R16") (pin "2") (pinfunction "2_2") (pintype "passive"))
      (node (ref "SB6") (pin "1") (pinfunction "1_1") (pintype "passive"))
    )
    (net (code "65") (name "Net-(R14-Pad1)") (class "Default")
      (node (ref "R14") (pin "1") (pinfunction "1_1") (pintype "passive"))
      (node (ref "R17") (pin "2") (pinfunction "2_2") (pintype "passive"))
      (node (ref "SB7") (pin "1") (pinfunction "1_1") (pintype "passive"))
    )
    (net (code "66") (name "Net-(R18-Pad2)") (class "Default")
      (node (ref "R18") (pin "2") (pinfunction "2_2") (pintype "passive"))
      (node (ref "SB8") (pin "1") (pinfunction "1_1") (pintype "passive"))
    )
    (net (code "67") (name "Net-(R19-Pad2)") (class "Default")
      (node (ref "R19") (pin "2") (pinfunction "2_2") (pintype "passive"))
      (node (ref "SB9") (pin "1") (pinfunction "1_1") (pintype "passive"))
    )
    (net (code "68") (name "Net-(R20-Pad2)") (class "Default")
      (node (ref "R20") (pin "2") (pinfunction "2_2") (pintype "passive"))
      (node (ref "SB10") (pin "1") (pinfunction "1_1") (pintype "passive"))
    )
    (net (code "69") (name "Net-(R21-Pad2)") (class "Default")
      (node (ref "R21") (pin "2") (pinfunction "2_2") (pintype "passive"))
      (node (ref "SB11") (pin "1") (pinfunction "1_1") (pintype "passive"))
    )
    (net (code "70") (name "Net-(R23-Pad2)") (class "Default")
      (node (ref "R23") (pin "2") (pinfunction "2_2") (pintype "passive"))
      (node (ref "UART_PWR") (pin "1") (pinfunction "1_1") (pintype "passive"))
    )
    (net (code "71") (name "Net-(U1A-PH1-OSC_OUT(PH1))") (class "Default")
      (node (ref "C11") (pin "2") (pinfunction "2_2") (pintype "passive"))
      (node (ref "U1") (pin "13") (pinfunction "PH1-OSC_OUT(PH1)_13") (pintype "bidirectional"))
      (node (ref "X1") (pin "2") (pintype "passive"))
    )
    (net (code "72") (name "Net-(U1A-VCAP_1)") (class "Default")
      (node (ref "C13") (pin "2") (pinfunction "2_2") (pintype "passive"))
      (node (ref "U1") (pin "49") (pinfunction "VCAP_1_49") (pintype "power_in"))
    )
    (net (code "73") (name "Net-(U1A-VCAP_2)") (class "Default")
      (node (ref "C12") (pin "2") (pinfunction "2_2") (pintype "passive"))
      (node (ref "U1") (pin "73") (pinfunction "VCAP_2_73") (pintype "power_in"))
    )
    (net (code "74") (name "Net-(U3-IN)") (class "Default")
      (node (ref "C16") (pin "1") (pinfunction "1_1") (pintype "passive"))
      (node (ref "LDO_ON") (pin "2") (pinfunction "2_2") (pintype "passive"))
      (node (ref "U3") (pin "1") (pinfunction "IN_1") (pintype "passive"))
    )
    (net (code "75") (name "unconnected-(BM_RESET-Pad1)") (class "Default")
      (node (ref "BM_RESET") (pin "1") (pinfunction "1_1") (pintype "passive"))
    )
    (net (code "76") (name "unconnected-(BM_RESET-Pad3)") (class "Default")
      (node (ref "BM_RESET") (pin "3") (pinfunction "3_3") (pintype "passive"))
    )
    (net (code "77") (name "unconnected-(J1-KEY-Pad7)") (class "Default")
      (node (ref "J1") (pin "7") (pinfunction "KEY_7") (pintype "passive"))
    )
    (net (code "78") (name "unconnected-(MCU_RESET-Pad1)") (class "Default")
      (node (ref "MCU_RESET") (pin "1") (pinfunction "1_1") (pintype "passive"))
    )
    (net (code "79") (name "unconnected-(MCU_RESET-Pad3)") (class "Default")
      (node (ref "MCU_RESET") (pin "3") (pinfunction "3_3") (pintype "passive"))
    )
    (net (code "80") (name "unconnected-(P2-Pad1)") (class "Default")
      (node (ref "P2") (pin "1") (pinfunction "1_1") (pintype "passive"))
    )
    (net (code "81") (name "unconnected-(P3-Pad1)") (class "Default")
      (node (ref "P3") (pin "1") (pinfunction "1_1") (pintype "passive"))
    )
    (net (code "82") (name "unconnected-(P4-Pad1)") (class "Default")
      (node (ref "P4") (pin "1") (pinfunction "1_1") (pintype "passive"))
    )
    (net (code "83") (name "unconnected-(P5-Pad1)") (class "Default")
      (node (ref "P5") (pin "1") (pinfunction "1_1") (pintype "passive"))
    )
    (net (code "84") (name "unconnected-(U1A-PA0-WKUP(PA0)-Pad23)") (class "Default")
      (node (ref "U1") (pin "23") (pinfunction "PA0-WKUP(PA0)_23") (pintype "bidirectional"))
    )
    (net (code "85") (name "unconnected-(U1A-PA3-Pad26)") (class "Default")
      (node (ref "U1") (pin "26") (pinfunction "PA3_26") (pintype "bidirectional"))
    )
    (net (code "86") (name "unconnected-(U1A-PA4-Pad29)") (class "Default")
      (node (ref "U1") (pin "29") (pinfunction "PA4_29") (pintype "bidirectional"))
    )
    (net (code "87") (name "unconnected-(U1A-PA7-Pad32)") (class "Default")
      (node (ref "U1") (pin "32") (pinfunction "PA7_32") (pintype "bidirectional"))
    )
    (net (code "88") (name "unconnected-(U1A-PA8-Pad67)") (class "Default")
      (node (ref "U1") (pin "67") (pinfunction "PA8_67") (pintype "bidirectional"))
    )
    (net (code "89") (name "unconnected-(U1A-PA11-Pad70)") (class "Default")
      (node (ref "U1") (pin "70") (pinfunction "PA11_70") (pintype "bidirectional"))
    )
    (net (code "90") (name "unconnected-(U1A-PA12-Pad71)") (class "Default")
      (node (ref "U1") (pin "71") (pinfunction "PA12_71") (pintype "bidirectional"))
    )
    (net (code "91") (name "unconnected-(U1A-PB0-Pad35)") (class "Default")
      (node (ref "U1") (pin "35") (pinfunction "PB0_35") (pintype "bidirectional"))
    )
    (net (code "92") (name "unconnected-(U1A-PB1-Pad36)") (class "Default")
      (node (ref "U1") (pin "36") (pinfunction "PB1_36") (pintype "bidirectional"))
    )
    (net (code "93") (name "unconnected-(U1A-PB2-BOOT1(PB2)-Pad37)") (class "Default")
      (node (ref "U1") (pin "37") (pinfunction "PB2-BOOT1(PB2)_37") (pintype "bidirectional"))
    )
    (net (code "94") (name "unconnected-(U1A-PB4(NJTRST)-Pad90)") (class "Default")
      (node (ref "U1") (pin "90") (pinfunction "PB4(NJTRST)_90") (pintype "bidirectional"))
    )
    (net (code "95") (name "unconnected-(U1A-PB5-Pad91)") (class "Default")
      (node (ref "U1") (pin "91") (pinfunction "PB5_91") (pintype "bidirectional"))
    )
    (net (code "96") (name "unconnected-(U1A-PB6-Pad92)") (class "Default")
      (node (ref "U1") (pin "92") (pinfunction "PB6_92") (pintype "bidirectional"))
    )
    (net (code "97") (name "unconnected-(U1A-PB7-Pad93)") (class "Default")
      (node (ref "U1") (pin "93") (pinfunction "PB7_93") (pintype "bidirectional"))
    )
    (net (code "98") (name "unconnected-(U1A-PB12-Pad51)") (class "Default")
      (node (ref "U1") (pin "51") (pinfunction "PB12_51") (pintype "bidirectional"))
    )
    (net (code "99") (name "unconnected-(U1A-PC0-Pad15)") (class "Default")
      (node (ref "U1") (pin "15") (pinfunction "PC0_15") (pintype "bidirectional"))
    )
    (net (code "100") (name "unconnected-(U1A-PC1-Pad16)") (class "Default")
      (node (ref "U1") (pin "16") (pinfunction "PC1_16") (pintype "bidirectional"))
    )
    (net (code "101") (name "unconnected-(U1A-PC2-Pad17)") (class "Default")
      (node (ref "U1") (pin "17") (pinfunction "PC2_17") (pintype "bidirectional"))
    )
    (net (code "102") (name "unconnected-(U1A-PC3-Pad18)") (class "Default")
      (node (ref "U1") (pin "18") (pinfunction "PC3_18") (pintype "bidirectional"))
    )
    (net (code "103") (name "unconnected-(U1A-PC10-Pad78)") (class "Default")
      (node (ref "U1") (pin "78") (pinfunction "PC10_78") (pintype "bidirectional"))
    )
    (net (code "104") (name "unconnected-(U1A-PC11-Pad79)") (class "Default")
      (node (ref "U1") (pin "79") (pinfunction "PC11_79") (pintype "bidirectional"))
    )
    (net (code "105") (name "unconnected-(U1A-PC12-Pad80)") (class "Default")
      (node (ref "U1") (pin "80") (pinfunction "PC12_80") (pintype "bidirectional"))
    )
    (net (code "106") (name "unconnected-(U1A-PC13-Pad7)") (class "Default")
      (node (ref "U1") (pin "7") (pinfunction "PC13_7") (pintype "bidirectional"))
    )
    (net (code "107") (name "unconnected-(U1A-PC14-OSC32_IN(PC14)-Pad8)") (class "Default")
      (node (ref "U1") (pin "8") (pinfunction "PC14-OSC32_IN(PC14)_8") (pintype "bidirectional"))
    )
    (net (code "108") (name "unconnected-(U1A-PC15-OSC32_OUT(PC15)-Pad9)") (class "Default")
      (node (ref "U1") (pin "9") (pinfunction "PC15-OSC32_OUT(PC15)_9") (pintype "bidirectional"))
    )
    (net (code "109") (name "unconnected-(U1A-PD0-Pad81)") (class "Default")
      (node (ref "U1") (pin "81") (pinfunction "PD0_81") (pintype "bidirectional"))
    )
    (net (code "110") (name "unconnected-(U1A-PD1-Pad82)") (class "Default")
      (node (ref "U1") (pin "82") (pinfunction "PD1_82") (pintype "bidirectional"))
    )
    (net (code "111") (name "unconnected-(U1A-PD2-Pad83)") (class "Default")
      (node (ref "U1") (pin "83") (pinfunction "PD2_83") (pintype "bidirectional"))
    )
    (net (code "112") (name "unconnected-(U1A-PD3-Pad84)") (class "Default")
      (node (ref "U1") (pin "84") (pinfunction "PD3_84") (pintype "bidirectional"))
    )
    (net (code "113") (name "unconnected-(U1A-PD4-Pad85)") (class "Default")
      (node (ref "U1") (pin "85") (pinfunction "PD4_85") (pintype "bidirectional"))
    )
    (net (code "114") (name "unconnected-(U1A-PD5-Pad86)") (class "Default")
      (node (ref "U1") (pin "86") (pinfunction "PD5_86") (pintype "bidirectional"))
    )
    (net (code "115") (name "unconnected-(U1A-PD6-Pad87)") (class "Default")
      (node (ref "U1") (pin "87") (pinfunction "PD6_87") (pintype "bidirectional"))
    )
    (net (code "116") (name "unconnected-(U1A-PD7-Pad88)") (class "Default")
      (node (ref "U1") (pin "88") (pinfunction "PD7_88") (pintype "bidirectional"))
    )
    (net (code "117") (name "unconnected-(U1A-PD8-Pad55)") (class "Default")
      (node (ref "U1") (pin "55") (pinfunction "PD8_55") (pintype "bidirectional"))
    )
    (net (code "118") (name "unconnected-(U1A-PD9-Pad56)") (class "Default")
      (node (ref "U1") (pin "56") (pinfunction "PD9_56") (pintype "bidirectional"))
    )
    (net (code "119") (name "unconnected-(U1A-PD10-Pad57)") (class "Default")
      (node (ref "U1") (pin "57") (pinfunction "PD10_57") (pintype "bidirectional"))
    )
    (net (code "120") (name "unconnected-(U1A-PD11-Pad58)") (class "Default")
      (node (ref "U1") (pin "58") (pinfunction "PD11_58") (pintype "bidirectional"))
    )
    (net (code "121") (name "unconnected-(U1A-PD12-Pad59)") (class "Default")
      (node (ref "U1") (pin "59") (pinfunction "PD12_59") (pintype "bidirectional"))
    )
    (net (code "122") (name "unconnected-(U1A-PD13-Pad60)") (class "Default")
      (node (ref "U1") (pin "60") (pinfunction "PD13_60") (pintype "bidirectional"))
    )
    (net (code "123") (name "unconnected-(U1A-PD14-Pad61)") (class "Default")
      (node (ref "U1") (pin "61") (pinfunction "PD14_61") (pintype "bidirectional"))
    )
    (net (code "124") (name "unconnected-(U1A-PD15-Pad62)") (class "Default")
      (node (ref "U1") (pin "62") (pinfunction "PD15_62") (pintype "bidirectional"))
    )
    (net (code "125") (name "unconnected-(U1A-PE4-Pad3)") (class "Default")
      (node (ref "U1") (pin "3") (pinfunction "PE4_3") (pintype "bidirectional"))
    )
    (net (code "126") (name "unconnected-(U1A-PE5-Pad4)") (class "Default")
      (node (ref "U1") (pin "4") (pinfunction "PE5_4") (pintype "bidirectional"))
    )
    (net (code "127") (name "unconnected-(U1A-PE6-Pad5)") (class "Default")
      (node (ref "U1") (pin "5") (pinfunction "PE6_5") (pintype "bidirectional"))
    )
    (net (code "128") (name "unconnected-(U1A-PE7-Pad38)") (class "Default")
      (node (ref "U1") (pin "38") (pinfunction "PE7_38") (pintype "bidirectional"))
    )
    (net (code "129") (name "unconnected-(U1A-PE8-Pad39)") (class "Default")
      (node (ref "U1") (pin "39") (pinfunction "PE8_39") (pintype "bidirectional"))
    )
    (net (code "130") (name "unconnected-(U1A-PE9-Pad40)") (class "Default")
      (node (ref "U1") (pin "40") (pinfunction "PE9_40") (pintype "bidirectional"))
    )
    (net (code "131") (name "unconnected-(U1A-PE10-Pad41)") (class "Default")
      (node (ref "U1") (pin "41") (pinfunction "PE10_41") (pintype "bidirectional"))
    )
    (net (code "132") (name "unconnected-(U1A-PE11-Pad42)") (class "Default")
      (node (ref "U1") (pin "42") (pinfunction "PE11_42") (pintype "bidirectional"))
    )
    (net (code "133") (name "unconnected-(U1A-PE12-Pad43)") (class "Default")
      (node (ref "U1") (pin "43") (pinfunction "PE12_43") (pintype "bidirectional"))
    )
    (net (code "134") (name "unconnected-(U1A-PE13-Pad44)") (class "Default")
      (node (ref "U1") (pin "44") (pinfunction "PE13_44") (pintype "bidirectional"))
    )
    (net (code "135") (name "unconnected-(U1A-PE14-Pad45)") (class "Default")
      (node (ref "U1") (pin "45") (pinfunction "PE14_45") (pintype "bidirectional"))
    )
    (net (code "136") (name "unconnected-(U2-NC-Pad1)") (class "Default")
      (node (ref "U2") (pin "1") (pinfunction "NC_1") (pintype "passive"))
    )
  )
)
